# mains_led3.net
KiCad netlist of a schematic drawn in EAGLE
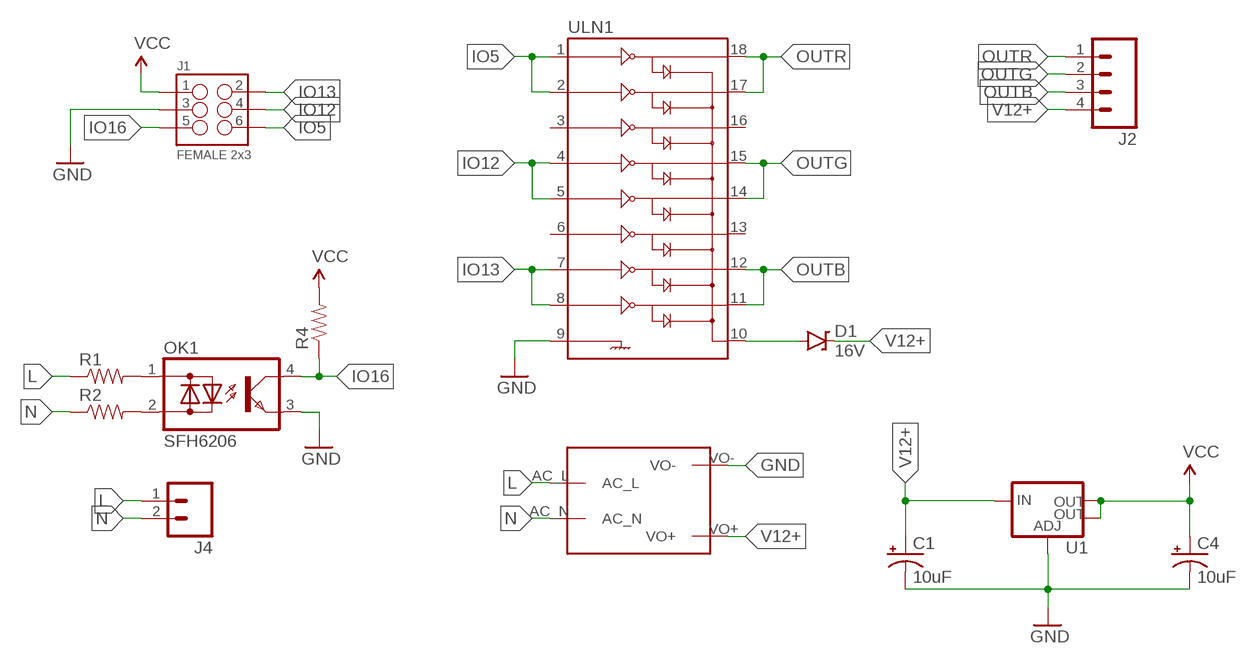
[diagram p0: schematic, sheet 1]

(export (version "E")
  (design (tool "Eeschema 10.0.6"))
  (components
    (comp (ref "C1")
      (value "10uF")
      (footprint "eagle-import:EIA3216-KIT")
      (libsource (lib "eagle-import") (part "CAP_POL1206-KIT"))
    )
    (comp (ref "C4")
      (value "10uF")
      (footprint "eagle-import:EIA3216-KIT")
      (libsource (lib "eagle-import") (part "CAP_POL1206-KIT"))
    )
    (comp (ref "D1")
      (value "16V")
      (footprint "eagle-import:SOD-123")
      (libsource (lib "eagle-import") (part "DIODE-ZENER16V"))
    )
    (comp (ref "J1")
      (value "FEMALE 2x3")
      (footprint "eagle-import:2X3-SHROUDED")
      (libsource (lib "eagle-import") (part "M03X2SHROUD"))
    )
    (comp (ref "J2")
      (value "M04NO_SILK_ALL_ROUND")
      (footprint "eagle-import:1X04_NO_SILK_ALL_ROUND")
      (libsource (lib "eagle-import") (part "M04NO_SILK_ALL_ROUND"))
    )
    (comp (ref "J4")
      (value "M023.5MM")
      (footprint "eagle-import:SCREWTERMINAL-3.5MM-2")
      (libsource (lib "eagle-import") (part "M023.5MM"))
    )
    (comp (ref "OK1")
      (value "SFH6206")
      (footprint "eagle-import:DIL4-SMD")
      (libsource (lib "eagle-import") (part "SFH6206"))
    )
    (comp (ref "R1")
      (value "RESISTORPTH-1/4W-VERT")
      (footprint "eagle-import:AXIAL-0.1")
      (libsource (lib "eagle-import") (part "RESISTORPTH-1/4W-VERT"))
    )
    (comp (ref "R2")
      (value "RESISTORPTH-1/4W-VERT")
      (footprint "eagle-import:AXIAL-0.1")
      (libsource (lib "eagle-import") (part "RESISTORPTH-1/4W-VERT"))
    )
    (comp (ref "R4")
      (value "RESISTOR0805-RES")
      (footprint "eagle-import:0805")
      (libsource (lib "eagle-import") (part "RESISTOR0805-RES"))
    )
    (comp (ref "U$1")
      (value "MAINS_CONVERTERS")
      (footprint "eagle-import:HLK-PM01")
      (libsource (lib "eagle-import") (part "MAINS_CONVERTERS"))
    )
    (comp (ref "U1")
      (value "V_REG_LM1117SOT223")
      (footprint "eagle-import:SOT223")
      (libsource (lib "eagle-import") (part "V_REG_LM1117SOT223"))
    )
    (comp (ref "ULN1")
      (value "ULN2803SOICW")
      (footprint "eagle-import:SO18L")
      (libsource (lib "eagle-import") (part "ULN2803SOICW"))
    )
  )
  (nets
    (net (code "1") (name "GND") (class "Default")
      (node (ref "C1") (pin "C") (pinfunction "-_C") (pintype "passive"))
      (node (ref "C4") (pin "C") (pinfunction "-_C") (pintype "passive"))
      (node (ref "J1") (pin "3") (pinfunction "3_3") (pintype "bidirectional"))
      (node (ref "OK1") (pin "3") (pinfunction "E_3") (pintype "passive"))
      (node (ref "U$1") (pin "VO-") (pinfunction "VO-_VO-") (pintype "output"))
      (node (ref "U1") (pin "1") (pinfunction "ADJ_1") (pintype "input"))
      (node (ref "ULN1") (pin "9") (pinfunction "9_9") (pintype "bidirectional"))
    )
    (net (code "2") (name "IO5") (class "Default")
      (node (ref "J1") (pin "6") (pinfunction "6_6") (pintype "bidirectional"))
      (node (ref "ULN1") (pin "1") (pinfunction "1_1") (pintype "bidirectional"))
      (node (ref "ULN1") (pin "2") (pinfunction "2_2") (pintype "bidirectional"))
    )
    (net (code "3") (name "IO12") (class "Default")
      (node (ref "J1") (pin "4") (pinfunction "4_4") (pintype "bidirectional"))
      (node (ref "ULN1") (pin "4") (pinfunction "4_4") (pintype "bidirectional"))
      (node (ref "ULN1") (pin "5") (pinfunction "5_5") (pintype "bidirectional"))
    )
    (net (code "4") (name "IO13") (class "Default")
      (node (ref "J1") (pin "2") (pinfunction "2_2") (pintype "bidirectional"))
      (node (ref "ULN1") (pin "7") (pinfunction "7_7") (pintype "bidirectional"))
      (node (ref "ULN1") (pin "8") (pinfunction "8_8") (pintype "bidirectional"))
    )
    (net (code "5") (name "IO16") (class "Default")
      (node (ref "J1") (pin "5") (pinfunction "5_5") (pintype "bidirectional"))
      (node (ref "OK1") (pin "4") (pinfunction "C_4") (pintype "passive"))
      (node (ref "R4") (pin "1") (pinfunction "1_1") (pintype "passive"))
    )
    (net (code "6") (name "L") (class "Default")
      (node (ref "J4") (pin "1") (pinfunction "1_1") (pintype "passive"))
      (node (ref "R1") (pin "P$1") (pinfunction "1_P$1") (pintype "passive"))
      (node (ref "U$1") (pin "AC_L") (pinfunction "AC_L_AC_L") (pintype "input"))
    )
    (net (code "7") (name "N") (class "Default")
      (node (ref "J4") (pin "2") (pinfunction "2_2") (pintype "passive"))
      (node (ref "R2") (pin "P$1") (pinfunction "1_P$1") (pintype "passive"))
      (node (ref "U$1") (pin "AC_N") (pinfunction "AC_N_AC_N") (pintype "input"))
    )
    (net (code "8") (name "Net-(D1-PadA)") (class "Default")
      (node (ref "D1") (pin "A") (pinfunction "A_A") (pintype "passive"))
      (node (ref "ULN1") (pin "10") (pinfunction "10_10") (pintype "bidirectional"))
    )
    (net (code "9") (name "Net-(OK1-AC1)") (class "Default")
      (node (ref "OK1") (pin "1") (pinfunction "AC1_1") (pintype "passive"))
      (node (ref "R1") (pin "P$2") (pinfunction "2_P$2") (pintype "passive"))
    )
    (net (code "10") (name "Net-(OK1-AC2)") (class "Default")
      (node (ref "OK1") (pin "2") (pinfunction "AC2_2") (pintype "passive"))
      (node (ref "R2") (pin "P$2") (pinfunction "2_P$2") (pintype "passive"))
    )
    (net (code "11") (name "OUTB") (class "Default")
      (node (ref "J2") (pin "3") (pinfunction "3_3") (pintype "passive"))
      (node (ref "ULN1") (pin "11") (pinfunction "11_11") (pintype "bidirectional"))
      (node (ref "ULN1") (pin "12") (pinfunction "12_12") (pintype "bidirectional"))
    )
    (net (code "12") (name "OUTG") (class "Default")
      (node (ref "J2") (pin "2") (pinfunction "2_2") (pintype "passive"))
      (node (ref "ULN1") (pin "14") (pinfunction "14_14") (pintype "bidirectional"))
      (node (ref "ULN1") (pin "15") (pinfunction "15_15") (pintype "bidirectional"))
    )
    (net (code "13") (name "OUTR") (class "Default")
      (node (ref "J2") (pin "1") (pinfunction "1_1") (pintype "passive"))
      (node (ref "ULN1") (pin "17") (pinfunction "17_17") (pintype "bidirectional"))
      (node (ref "ULN1") (pin "18") (pinfunction "18_18") (pintype "bidirectional"))
    )
    (net (code "14") (name "V12+") (class "Default")
      (node (ref "C1") (pin "A") (pinfunction "+_A") (pintype "passive"))
      (node (ref "D1") (pin "C") (pinfunction "C_C") (pintype "passive"))
      (node (ref "J2") (pin "4") (pinfunction "4_4") (pintype "passive"))
      (node (ref "U$1") (pin "VO+") (pinfunction "VO+_VO+") (pintype "output"))
      (node (ref "U1") (pin "3") (pinfunction "IN_3") (pintype "input"))
    )
    (net (code "15") (name "VCC") (class "Default")
      (node (ref "C4") (pin "A") (pinfunction "+_A") (pintype "passive"))
      (node (ref "J1") (pin "1") (pinfunction "1_1") (pintype "bidirectional"))
      (node (ref "R4") (pin "2") (pinfunction "2_2") (pintype "passive"))
      (node (ref "U1") (pin "2") (pinfunction "OUT_2") (pintype "output"))
      (node (ref "U1") (pin "4") (pinfunction "OUT_4") (pintype "output"))
    )
    (net (code "16") (name "unconnected-(ULN1-Pad3)") (class "Default")
      (node (ref "ULN1") (pin "3") (pinfunction "3_3") (pintype "bidirectional"))
    )
    (net (code "17") (name "unconnected-(ULN1-Pad6)") (class "Default")
      (node (ref "ULN1") (pin "6") (pinfunction "6_6") (pintype "bidirectional"))
    )
    (net (code "18") (name "unconnected-(ULN1-Pad13)") (class "Default")
      (node (ref "ULN1") (pin "13") (pinfunction "13_13") (pintype "bidirectional"))
    )
    (net (code "19") (name "unconnected-(ULN1-Pad16)") (class "Default")
      (node (ref "ULN1") (pin "16") (pinfunction "16_16") (pintype "bidirectional"))
    )
  )
)
